# CM4.net
KiCad netlist of a schematic drawn in Altium Designer
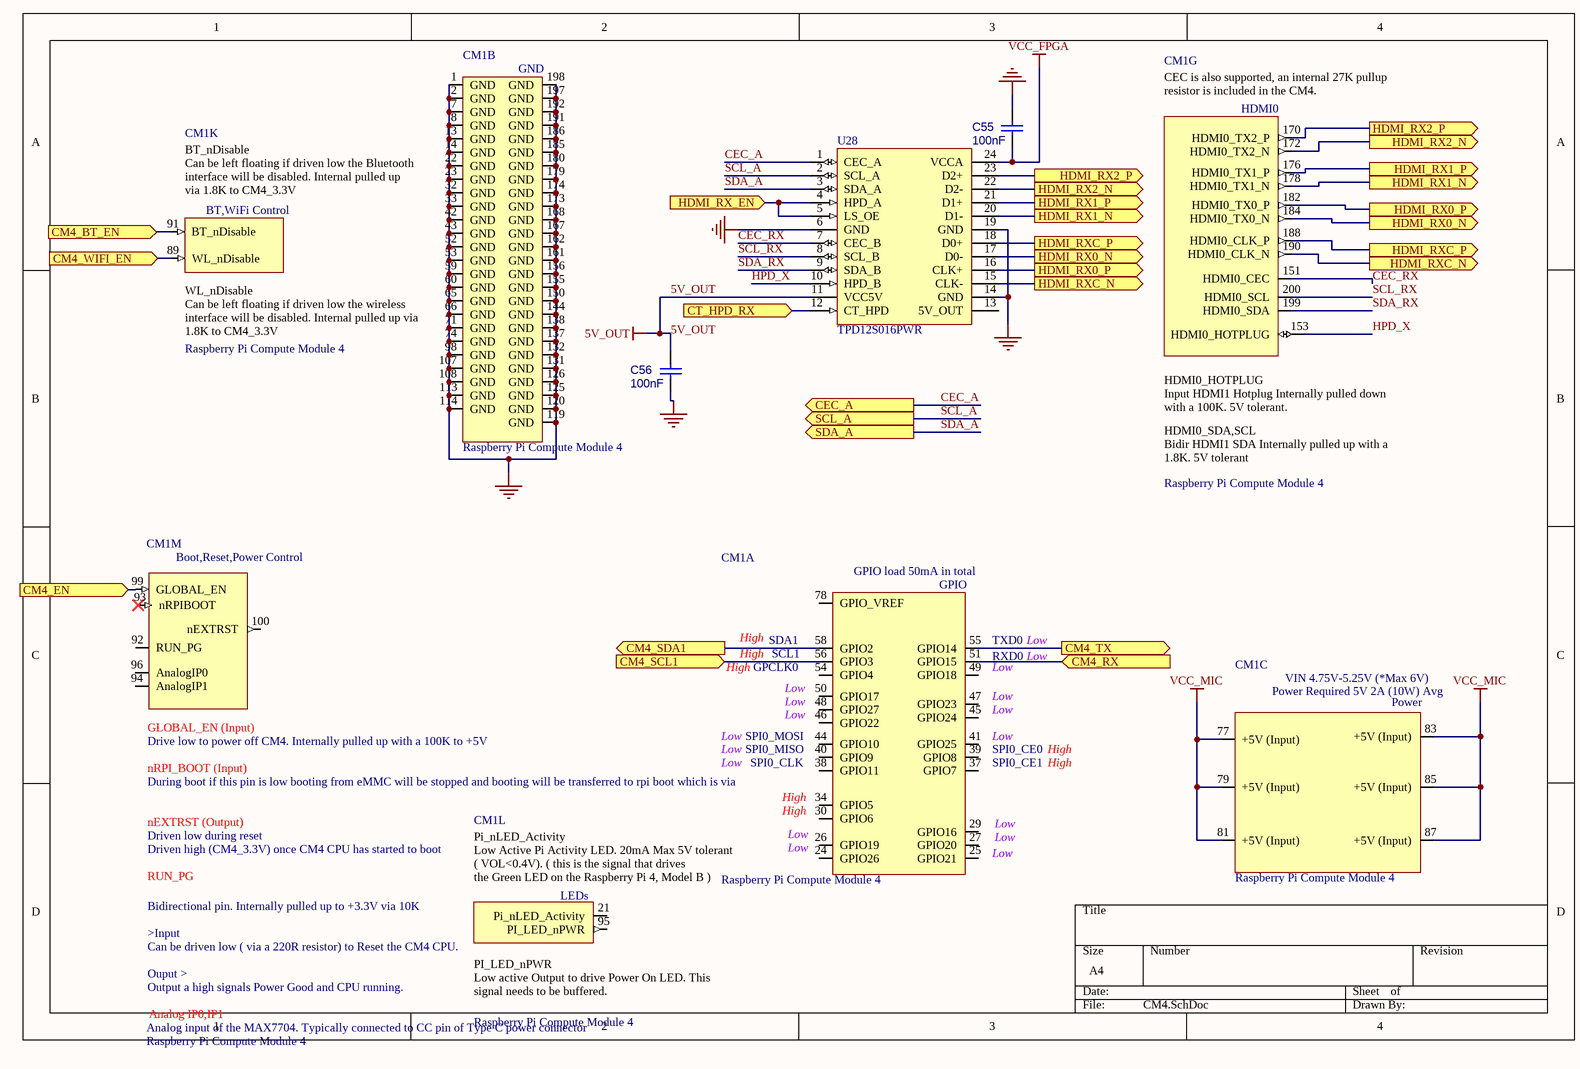
[diagram p0: CM4.SchDoc]

(export (version "E")
  (design (tool "Eeschema 10.0.6"))
  (components
    (comp (ref "C55")
      (value "100nF")
      (footprint "0603_CAP UF HD")
      (description "Capacitor")
      (libsource (lib "Workshop Library 2010_06_24") (part "Cap"))
    )
    (comp (ref "C56")
      (value "100nF")
      (footprint "0603_CAP UF HD")
      (description "Capacitor")
      (libsource (lib "Workshop Library 2010_06_24") (part "Cap"))
    )
    (comp (ref "CM1")
      (value "Raspberry Pi Compute Module 4")
      (footprint "CM4-F40C-100DS-0.4v_1.5mm_0mm")
      (description "Raspberry Pi Compute Module 4 by Amornthep Phunsin")
      (libsource (lib "CM4") (part "CM4"))
    )
    (comp (ref "U28")
      (value "TPD12S016PWR")
      (footprint "SOP65P640X120-24N")
      (libsource (lib "TE0765") (part "TPD12S016PWR"))
    )
  )
  (nets
    (net (code "1") (name "/CEC_A") (class "Default")
      (node (ref "U28") (pin "1") (pinfunction "CEC_A_1") (pintype "bidirectional"))
    )
    (net (code "2") (name "/CEC_RX") (class "Default")
      (node (ref "CM1") (pin "151") (pinfunction "HDMI0_CEC_151") (pintype "open_collector"))
      (node (ref "U28") (pin "7") (pinfunction "CEC_B_7") (pintype "bidirectional"))
    )
    (net (code "3") (name "/CM4_BT_EN") (class "Default")
      (node (ref "CM1") (pin "91") (pinfunction "BT_nDisable_91") (pintype "input"))
    )
    (net (code "4") (name "/CM4_EN") (class "Default")
      (node (ref "CM1") (pin "99") (pinfunction "GLOBAL_EN_99") (pintype "input"))
    )
    (net (code "5") (name "/CM4_RX") (class "Default")
      (node (ref "CM1") (pin "51") (pinfunction "GPIO15_51") (pintype "passive"))
    )
    (net (code "6") (name "/CM4_SCL1") (class "Default")
      (node (ref "CM1") (pin "56") (pinfunction "GPIO3_56") (pintype "passive"))
    )
    (net (code "7") (name "/CM4_SDA1") (class "Default")
      (node (ref "CM1") (pin "58") (pinfunction "GPIO2_58") (pintype "passive"))
    )
    (net (code "8") (name "/CM4_TX") (class "Default")
      (node (ref "CM1") (pin "55") (pinfunction "GPIO14_55") (pintype "passive"))
    )
    (net (code "9") (name "/CM4_WIFI_EN") (class "Default")
      (node (ref "CM1") (pin "89") (pinfunction "WL_nDisable_89") (pintype "input"))
    )
    (net (code "10") (name "/CT_HPD_RX") (class "Default")
      (node (ref "U28") (pin "12") (pinfunction "CT_HPD_12") (pintype "input"))
    )
    (net (code "11") (name "/HDMI_RX0_N") (class "Default")
      (node (ref "CM1") (pin "184") (pinfunction "HDMI0_TX0_N_184") (pintype "output"))
      (node (ref "U28") (pin "17") (pinfunction "D0-_17") (pintype "passive"))
    )
    (net (code "12") (name "/HDMI_RX0_P") (class "Default")
      (node (ref "CM1") (pin "182") (pinfunction "HDMI0_TX0_P_182") (pintype "output"))
      (node (ref "U28") (pin "16") (pinfunction "CLK+_16") (pintype "passive"))
    )
    (net (code "13") (name "/HDMI_RX1_N") (class "Default")
      (node (ref "CM1") (pin "178") (pinfunction "HDMI0_TX1_N_178") (pintype "output"))
      (node (ref "U28") (pin "20") (pinfunction "D1-_20") (pintype "passive"))
    )
    (net (code "14") (name "/HDMI_RX1_P") (class "Default")
      (node (ref "CM1") (pin "176") (pinfunction "HDMI0_TX1_P_176") (pintype "output"))
      (node (ref "U28") (pin "21") (pinfunction "D1+_21") (pintype "passive"))
    )
    (net (code "15") (name "/HDMI_RX2_N") (class "Default")
      (node (ref "CM1") (pin "172") (pinfunction "HDMI0_TX2_N_172") (pintype "output"))
      (node (ref "U28") (pin "22") (pinfunction "D2-_22") (pintype "passive"))
    )
    (net (code "16") (name "/HDMI_RX2_P") (class "Default")
      (node (ref "CM1") (pin "170") (pinfunction "HDMI0_TX2_P_170") (pintype "output"))
      (node (ref "U28") (pin "23") (pinfunction "D2+_23") (pintype "passive"))
    )
    (net (code "17") (name "/HDMI_RXC_N") (class "Default")
      (node (ref "CM1") (pin "190") (pinfunction "HDMI0_CLK_N_190") (pintype "output"))
      (node (ref "U28") (pin "15") (pinfunction "CLK-_15") (pintype "passive"))
    )
    (net (code "18") (name "/HDMI_RXC_P") (class "Default")
      (node (ref "CM1") (pin "188") (pinfunction "HDMI0_CLK_P_188") (pintype "output"))
      (node (ref "U28") (pin "18") (pinfunction "D0+_18") (pintype "passive"))
    )
    (net (code "19") (name "/HDMI_RX_EN") (class "Default")
      (node (ref "U28") (pin "4") (pinfunction "HPD_A_4") (pintype "input"))
      (node (ref "U28") (pin "5") (pinfunction "LS_OE_5") (pintype "input"))
    )
    (net (code "20") (name "/HPD_X") (class "Default")
      (node (ref "CM1") (pin "153") (pinfunction "HDMI0_HOTPLUG_153") (pintype "bidirectional"))
      (node (ref "U28") (pin "10") (pinfunction "HPD_B_10") (pintype "input"))
    )
    (net (code "21") (name "/SCL_A") (class "Default")
      (node (ref "U28") (pin "2") (pinfunction "SCL_A_2") (pintype "bidirectional"))
    )
    (net (code "22") (name "/SCL_RX") (class "Default")
      (node (ref "CM1") (pin "200") (pinfunction "HDMI0_SCL_200") (pintype "open_collector"))
      (node (ref "U28") (pin "8") (pinfunction "SCL_B_8") (pintype "bidirectional"))
    )
    (net (code "23") (name "/SDA_A") (class "Default")
      (node (ref "U28") (pin "3") (pinfunction "SDA_A_3") (pintype "bidirectional"))
    )
    (net (code "24") (name "/SDA_RX") (class "Default")
      (node (ref "CM1") (pin "199") (pinfunction "HDMI0_SDA_199") (pintype "bidirectional"))
      (node (ref "U28") (pin "9") (pinfunction "SDA_B_9") (pintype "bidirectional"))
    )
    (net (code "25") (name "5V_OUT") (class "Default")
      (node (ref "C56") (pin "1") (pinfunction "1_1") (pintype "passive"))
      (node (ref "U28") (pin "11") (pinfunction "VCC5V_11") (pintype "power_in"))
    )
    (net (code "26") (name "GND") (class "Default")
      (node (ref "C55") (pin "1") (pinfunction "1_1") (pintype "passive"))
      (node (ref "C56") (pin "2") (pinfunction "2_2") (pintype "passive"))
      (node (ref "CM1") (pin "1") (pinfunction "GND_1") (pintype "power_in"))
      (node (ref "CM1") (pin "107") (pinfunction "GND_107") (pintype "power_in"))
      (node (ref "CM1") (pin "108") (pinfunction "GND_108") (pintype "power_in"))
      (node (ref "CM1") (pin "113") (pinfunction "GND_113") (pintype "power_in"))
      (node (ref "CM1") (pin "114") (pinfunction "GND_114") (pintype "power_in"))
      (node (ref "CM1") (pin "119") (pinfunction "GND_119") (pintype "power_in"))
      (node (ref "CM1") (pin "120") (pinfunction "GND_120") (pintype "power_in"))
      (node (ref "CM1") (pin "125") (pinfunction "GND_125") (pintype "power_in"))
      (node (ref "CM1") (pin "126") (pinfunction "GND_126") (pintype "power_in"))
      (node (ref "CM1") (pin "13") (pinfunction "GND_13") (pintype "power_in"))
      (node (ref "CM1") (pin "131") (pinfunction "GND_131") (pintype "power_in"))
      (node (ref "CM1") (pin "132") (pinfunction "GND_132") (pintype "power_in"))
      (node (ref "CM1") (pin "137") (pinfunction "GND_137") (pintype "power_in"))
      (node (ref "CM1") (pin "138") (pinfunction "GND_138") (pintype "power_in"))
      (node (ref "CM1") (pin "14") (pinfunction "GND_14") (pintype "power_in"))
      (node (ref "CM1") (pin "144") (pinfunction "GND_144") (pintype "power_in"))
      (node (ref "CM1") (pin "150") (pinfunction "GND_150") (pintype "power_in"))
      (node (ref "CM1") (pin "155") (pinfunction "GND_155") (pintype "power_in"))
      (node (ref "CM1") (pin "156") (pinfunction "GND_156") (pintype "power_in"))
      (node (ref "CM1") (pin "161") (pinfunction "GND_161") (pintype "power_in"))
      (node (ref "CM1") (pin "162") (pinfunction "GND_162") (pintype "power_in"))
      (node (ref "CM1") (pin "167") (pinfunction "GND_167") (pintype "power_in"))
      (node (ref "CM1") (pin "168") (pinfunction "GND_168") (pintype "power_in"))
      (node (ref "CM1") (pin "173") (pinfunction "GND_173") (pintype "power_in"))
      (node (ref "CM1") (pin "174") (pinfunction "GND_174") (pintype "power_in"))
      (node (ref "CM1") (pin "179") (pinfunction "GND_179") (pintype "power_in"))
      (node (ref "CM1") (pin "180") (pinfunction "GND_180") (pintype "power_in"))
      (node (ref "CM1") (pin "185") (pinfunction "GND_185") (pintype "power_in"))
      (node (ref "CM1") (pin "186") (pinfunction "GND_186") (pintype "power_in"))
      (node (ref "CM1") (pin "191") (pinfunction "GND_191") (pintype "power_in"))
      (node (ref "CM1") (pin "192") (pinfunction "GND_192") (pintype "power_in"))
      (node (ref "CM1") (pin "197") (pinfunction "GND_197") (pintype "power_in"))
      (node (ref "CM1") (pin "198") (pinfunction "GND_198") (pintype "power_in"))
      (node (ref "CM1") (pin "2") (pinfunction "GND_2") (pintype "power_in"))
      (node (ref "CM1") (pin "22") (pinfunction "GND_22") (pintype "power_in"))
      (node (ref "CM1") (pin "23") (pinfunction "GND_23") (pintype "power_in"))
      (node (ref "CM1") (pin "32") (pinfunction "GND_32") (pintype "power_in"))
      (node (ref "CM1") (pin "33") (pinfunction "GND_33") (pintype "power_in"))
      (node (ref "CM1") (pin "42") (pinfunction "GND_42") (pintype "power_in"))
      (node (ref "CM1") (pin "43") (pinfunction "GND_43") (pintype "power_in"))
      (node (ref "CM1") (pin "52") (pinfunction "GND_52") (pintype "power_in"))
      (node (ref "CM1") (pin "53") (pinfunction "GND_53") (pintype "power_in"))
      (node (ref "CM1") (pin "59") (pinfunction "GND_59") (pintype "power_in"))
      (node (ref "CM1") (pin "60") (pinfunction "GND_60") (pintype "power_in"))
      (node (ref "CM1") (pin "65") (pinfunction "GND_65") (pintype "power_in"))
      (node (ref "CM1") (pin "66") (pinfunction "GND_66") (pintype "power_in"))
      (node (ref "CM1") (pin "7") (pinfunction "GND_7") (pintype "power_in"))
      (node (ref "CM1") (pin "71") (pinfunction "GND_71") (pintype "power_in"))
      (node (ref "CM1") (pin "74") (pinfunction "GND_74") (pintype "power_in"))
      (node (ref "CM1") (pin "8") (pinfunction "GND_8") (pintype "power_in"))
      (node (ref "CM1") (pin "98") (pinfunction "GND_98") (pintype "power_in"))
      (node (ref "U28") (pin "14") (pinfunction "GND_14") (pintype "passive"))
      (node (ref "U28") (pin "19") (pinfunction "GND_19") (pintype "power_in"))
      (node (ref "U28") (pin "6") (pinfunction "GND_6") (pintype "power_in"))
    )
    (net (code "27") (name "VCC_FPGA") (class "Default")
      (node (ref "C55") (pin "2") (pinfunction "2_2") (pintype "passive"))
      (node (ref "U28") (pin "24") (pinfunction "VCCA_24") (pintype "power_in"))
    )
    (net (code "28") (name "VCC_MIC") (class "Default")
      (node (ref "CM1") (pin "77") (pinfunction "+5V_(Input)_77") (pintype "power_in"))
      (node (ref "CM1") (pin "79") (pinfunction "+5V_(Input)_79") (pintype "power_in"))
      (node (ref "CM1") (pin "81") (pinfunction "+5V_(Input)_81") (pintype "power_in"))
      (node (ref "CM1") (pin "83") (pinfunction "+5V_(Input)_83") (pintype "power_in"))
      (node (ref "CM1") (pin "85") (pinfunction "+5V_(Input)_85") (pintype "power_in"))
      (node (ref "CM1") (pin "87") (pinfunction "+5V_(Input)_87") (pintype "power_in"))
    )
    (net (code "29") (name "unconnected-(CM1A-GPIO4-Pad54)") (class "Default")
      (node (ref "CM1") (pin "54") (pinfunction "GPIO4_54") (pintype "passive"))
    )
    (net (code "30") (name "unconnected-(CM1A-GPIO5-Pad34)") (class "Default")
      (node (ref "CM1") (pin "34") (pinfunction "GPIO5_34") (pintype "passive"))
    )
    (net (code "31") (name "unconnected-(CM1A-GPIO6-Pad30)") (class "Default")
      (node (ref "CM1") (pin "30") (pinfunction "GPIO6_30") (pintype "passive"))
    )
    (net (code "32") (name "unconnected-(CM1A-GPIO7-Pad37)") (class "Default")
      (node (ref "CM1") (pin "37") (pinfunction "GPIO7_37") (pintype "passive"))
    )
    (net (code "33") (name "unconnected-(CM1A-GPIO8-Pad39)") (class "Default")
      (node (ref "CM1") (pin "39") (pinfunction "GPIO8_39") (pintype "passive"))
    )
    (net (code "34") (name "unconnected-(CM1A-GPIO9-Pad40)") (class "Default")
      (node (ref "CM1") (pin "40") (pinfunction "GPIO9_40") (pintype "passive"))
    )
    (net (code "35") (name "unconnected-(CM1A-GPIO10-Pad44)") (class "Default")
      (node (ref "CM1") (pin "44") (pinfunction "GPIO10_44") (pintype "passive"))
    )
    (net (code "36") (name "unconnected-(CM1A-GPIO11-Pad38)") (class "Default")
      (node (ref "CM1") (pin "38") (pinfunction "GPIO11_38") (pintype "passive"))
    )
    (net (code "37") (name "unconnected-(CM1A-GPIO16-Pad29)") (class "Default")
      (node (ref "CM1") (pin "29") (pinfunction "GPIO16_29") (pintype "passive"))
    )
    (net (code "38") (name "unconnected-(CM1A-GPIO17-Pad50)") (class "Default")
      (node (ref "CM1") (pin "50") (pinfunction "GPIO17_50") (pintype "passive"))
    )
    (net (code "39") (name "unconnected-(CM1A-GPIO18-Pad49)") (class "Default")
      (node (ref "CM1") (pin "49") (pinfunction "GPIO18_49") (pintype "passive"))
    )
    (net (code "40") (name "unconnected-(CM1A-GPIO19-Pad26)") (class "Default")
      (node (ref "CM1") (pin "26") (pinfunction "GPIO19_26") (pintype "passive"))
    )
    (net (code "41") (name "unconnected-(CM1A-GPIO20-Pad27)") (class "Default")
      (node (ref "CM1") (pin "27") (pinfunction "GPIO20_27") (pintype "passive"))
    )
    (net (code "42") (name "unconnected-(CM1A-GPIO21-Pad25)") (class "Default")
      (node (ref "CM1") (pin "25") (pinfunction "GPIO21_25") (pintype "passive"))
    )
    (net (code "43") (name "unconnected-(CM1A-GPIO22-Pad46)") (class "Default")
      (node (ref "CM1") (pin "46") (pinfunction "GPIO22_46") (pintype "passive"))
    )
    (net (code "44") (name "unconnected-(CM1A-GPIO23-Pad47)") (class "Default")
      (node (ref "CM1") (pin "47") (pinfunction "GPIO23_47") (pintype "passive"))
    )
    (net (code "45") (name "unconnected-(CM1A-GPIO24-Pad45)") (class "Default")
      (node (ref "CM1") (pin "45") (pinfunction "GPIO24_45") (pintype "passive"))
    )
    (net (code "46") (name "unconnected-(CM1A-GPIO25-Pad41)") (class "Default")
      (node (ref "CM1") (pin "41") (pinfunction "GPIO25_41") (pintype "passive"))
    )
    (net (code "47") (name "unconnected-(CM1A-GPIO26-Pad24)") (class "Default")
      (node (ref "CM1") (pin "24") (pinfunction "GPIO26_24") (pintype "passive"))
    )
    (net (code "48") (name "unconnected-(CM1A-GPIO27-Pad48)") (class "Default")
      (node (ref "CM1") (pin "48") (pinfunction "GPIO27_48") (pintype "passive"))
    )
    (net (code "49") (name "unconnected-(CM1A-GPIO_VREF-Pad78)") (class "Default")
      (node (ref "CM1") (pin "78") (pinfunction "GPIO_VREF_78") (pintype "power_in"))
    )
    (net (code "50") (name "unconnected-(CM1L-PI_LED_nPWR-Pad95)") (class "Default")
      (node (ref "CM1") (pin "95") (pinfunction "PI_LED_nPWR_95") (pintype "output"))
    )
    (net (code "51") (name "unconnected-(CM1L-Pi_nLED_Activity-Pad21)") (class "Default")
      (node (ref "CM1") (pin "21") (pinfunction "Pi_nLED_Activity_21") (pintype "open_collector"))
    )
    (net (code "52") (name "unconnected-(CM1M-AnalogIP0-Pad96)") (class "Default")
      (node (ref "CM1") (pin "96") (pinfunction "AnalogIP0_96") (pintype "passive"))
    )
    (net (code "53") (name "unconnected-(CM1M-AnalogIP1-Pad94)") (class "Default")
      (node (ref "CM1") (pin "94") (pinfunction "AnalogIP1_94") (pintype "passive"))
    )
    (net (code "54") (name "unconnected-(CM1M-RUN_PG-Pad92)") (class "Default")
      (node (ref "CM1") (pin "92") (pinfunction "RUN_PG_92") (pintype "passive"))
    )
    (net (code "55") (name "unconnected-(CM1M-nEXTRST-Pad100)") (class "Default")
      (node (ref "CM1") (pin "100") (pinfunction "nEXTRST_100") (pintype "output"))
    )
    (net (code "56") (name "unconnected-(CM1M-nRPIBOOT-Pad93)") (class "Default")
      (node (ref "CM1") (pin "93") (pinfunction "nRPIBOOT_93") (pintype "input+no_connect"))
    )
    (net (code "57") (name "unconnected-(U28-5V_OUT-Pad13)") (class "Default")
      (node (ref "U28") (pin "13") (pinfunction "5V_OUT_13") (pintype "power_in"))
    )
  )
)
